# LCmeter0-perfboard-new.net
KiCad netlist of a schematic drawn in EAGLE
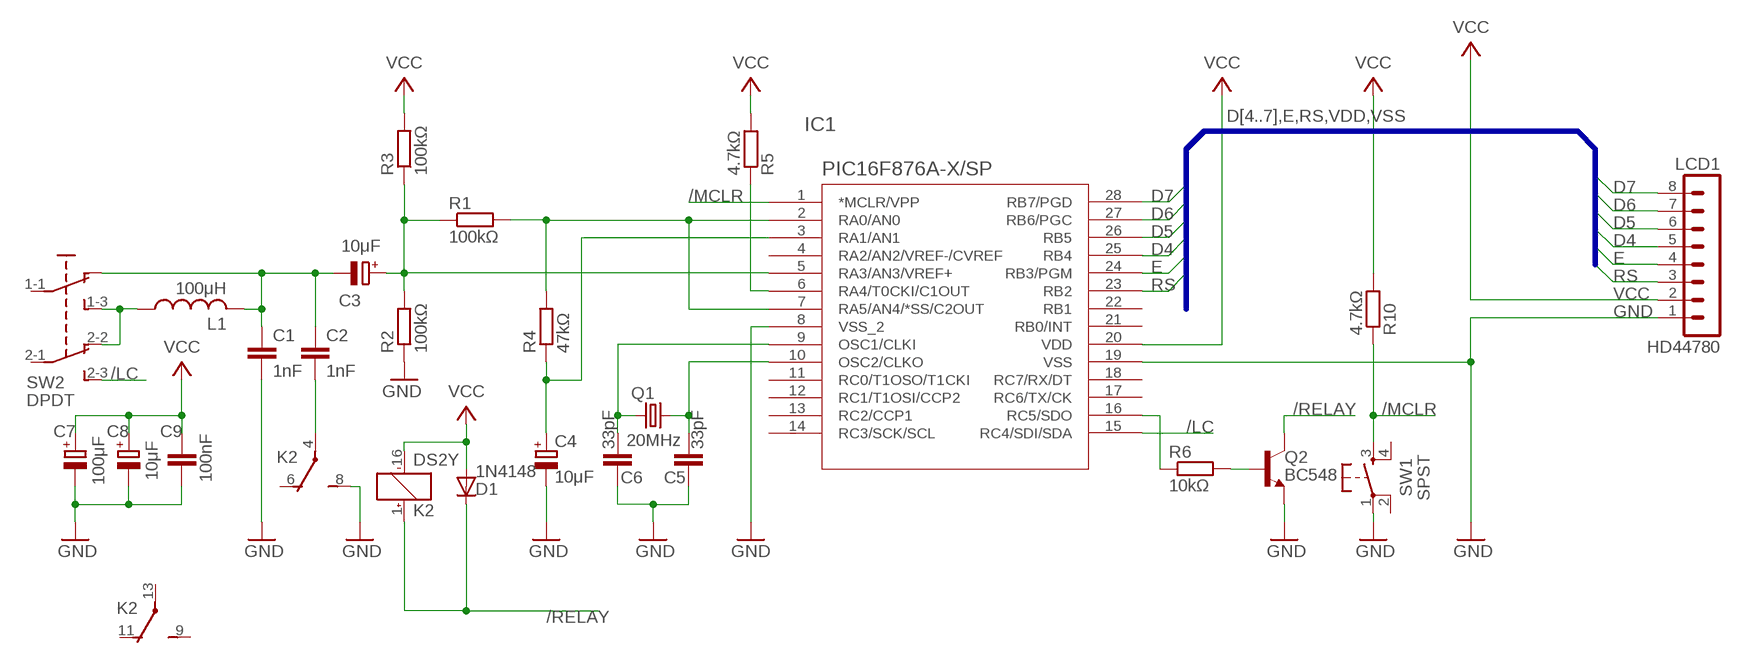
[diagram p0: schematic, sheet 1]

(export (version "E")
  (design (tool "Eeschema 10.0.6"))
  (components
    (comp (ref "C1")
      (value "1nF")
      (footprint "eagle-import:C050-024X044")
      (libsource (lib "eagle-import") (part "C-EU050-024X044"))
    )
    (comp (ref "C2")
      (value "1nF")
      (footprint "eagle-import:C050-024X044")
      (libsource (lib "eagle-import") (part "C-EU050-024X044"))
    )
    (comp (ref "C3")
      (value "10μF")
      (footprint "eagle-import:E5-4")
      (libsource (lib "eagle-import") (part "CPOL-EUE5-4"))
    )
    (comp (ref "C4")
      (value "10μF")
      (footprint "eagle-import:E5-4")
      (libsource (lib "eagle-import") (part "CPOL-EUE5-4"))
    )
    (comp (ref "C5")
      (value "33pF")
      (footprint "eagle-import:C050-024X044")
      (libsource (lib "eagle-import") (part "C-EU050-024X044"))
    )
    (comp (ref "C6")
      (value "33pF")
      (footprint "eagle-import:C050-024X044")
      (libsource (lib "eagle-import") (part "C-EU050-024X044"))
    )
    (comp (ref "C7")
      (value "100μF")
      (footprint "eagle-import:E2,5-6")
      (libsource (lib "eagle-import") (part "CPOL-EUE2.5-6"))
    )
    (comp (ref "C8")
      (value "10μF")
      (footprint "eagle-import:E2,5-5")
      (libsource (lib "eagle-import") (part "CPOL-EUE2.5-5"))
    )
    (comp (ref "C9")
      (value "100nF")
      (footprint "eagle-import:C025-024X044")
      (libsource (lib "eagle-import") (part "C-EU025-024X044"))
    )
    (comp (ref "D1")
      (value "1N4148")
      (footprint "eagle-import:DO35-7")
      (libsource (lib "eagle-import") (part "1N4148DO35-7"))
    )
    (comp (ref "IC1")
      (value "PIC16F876A-X/SP")
      (footprint "eagle-import:DIL28-3")
      (libsource (lib "eagle-import") (part "PIC16F876A-X/SP"))
    )
    (comp (ref "K2")
      (value "DS2Y")
      (footprint "eagle-import:DS2Y")
      (fields (field (name "MPN") "DS2Y-S-DC5V"))
      (libsource (lib "eagle-import") (part "DS2Y-S-DC5V"))
    )
    (comp (ref "L1")
      (value "100μH")
      (footprint "eagle-import:0204_5")
      (libsource (lib "eagle-import") (part "L-US0204/5"))
    )
    (comp (ref "LCD1")
      (value "HD44780")
      (footprint "eagle-import:MA08-1")
      (libsource (lib "eagle-import") (part "MA08-1"))
    )
    (comp (ref "Q1")
      (value "20MHz")
      (footprint "eagle-import:HC49_S")
      (libsource (lib "eagle-import") (part "CRYSTALHC49S"))
    )
    (comp (ref "Q2")
      (value "BC548")
      (footprint "eagle-import:TO92-EBC")
      (libsource (lib "eagle-import") (part "BC548"))
    )
    (comp (ref "R1")
      (value "100kΩ")
      (footprint "eagle-import:0204_7")
      (libsource (lib "eagle-import") (part "R-EU_0204/7"))
    )
    (comp (ref "R2")
      (value "100kΩ")
      (footprint "eagle-import:0204V")
      (libsource (lib "eagle-import") (part "resistor_R-EU_0204/2V"))
    )
    (comp (ref "R3")
      (value "100kΩ")
      (footprint "eagle-import:0204V")
      (libsource (lib "eagle-import") (part "resistor_R-EU_0204/2V"))
    )
    (comp (ref "R4")
      (value "47kΩ")
      (footprint "eagle-import:0204V")
      (libsource (lib "eagle-import") (part "resistor_R-EU_0204/2V"))
    )
    (comp (ref "R5")
      (value "4.7kΩ")
      (footprint "eagle-import:0207_10")
      (libsource (lib "eagle-import") (part "resistor_R-EU_0207/10"))
    )
    (comp (ref "R6")
      (value "10kΩ")
      (footprint "eagle-import:0204V")
      (libsource (lib "eagle-import") (part "resistor_R-EU_0204/2V"))
    )
    (comp (ref "R10")
      (value "4.7kΩ")
      (footprint "eagle-import:0207_10")
      (libsource (lib "eagle-import") (part "resistor_R-EU_0207/10"))
    )
    (comp (ref "SW1")
      (value "SPST")
      (footprint "eagle-import:PB-5")
      (libsource (lib "eagle-import") (part "PB-SPST"))
    )
    (comp (ref "SW2")
      (value "DPDT")
      (footprint "eagle-import:DPDT")
      (libsource (lib "eagle-import") (part "S-DPDT"))
    )
  )
  (nets
    (net (code "3") (name "/D4") (class "Default")
      (node (ref "IC1") (pin "25") (pinfunction "RB4_25") (pintype "passive"))
      (node (ref "LCD1") (pin "5") (pinfunction "5_5") (pintype "passive"))
    )
    (net (code "4") (name "/D5") (class "Default")
      (node (ref "IC1") (pin "26") (pinfunction "RB5_26") (pintype "passive"))
      (node (ref "LCD1") (pin "6") (pinfunction "6_6") (pintype "passive"))
    )
    (net (code "5") (name "/D6") (class "Default")
      (node (ref "IC1") (pin "27") (pinfunction "RB6/PGC_27") (pintype "passive"))
      (node (ref "LCD1") (pin "7") (pinfunction "7_7") (pintype "passive"))
    )
    (net (code "6") (name "/D7") (class "Default")
      (node (ref "IC1") (pin "28") (pinfunction "RB7/PGD_28") (pintype "passive"))
      (node (ref "LCD1") (pin "8") (pinfunction "8_8") (pintype "passive"))
    )
    (net (code "7") (name "/E") (class "Default")
      (node (ref "IC1") (pin "24") (pinfunction "RB3/PGM_24") (pintype "passive"))
      (node (ref "LCD1") (pin "4") (pinfunction "4_4") (pintype "passive"))
    )
    (net (code "8") (name "/RS") (class "Default")
      (node (ref "IC1") (pin "23") (pinfunction "RB2_23") (pintype "passive"))
      (node (ref "LCD1") (pin "3") (pinfunction "3_3") (pintype "passive"))
    )
    (net (code "10") (name "/{slash}LC") (class "Default")
      (node (ref "IC1") (pin "15") (pinfunction "RC4/SDI/SDA_15") (pintype "passive"))
      (node (ref "SW2") (pin "2-3") (pinfunction "2-3_2-3") (pintype "passive"))
    )
    (net (code "11") (name "/{slash}MCLR") (class "Default")
      (node (ref "IC1") (pin "1") (pinfunction "*MCLR/VPP_1") (pintype "passive"))
      (node (ref "R10") (pin "1") (pinfunction "1_1") (pintype "passive"))
      (node (ref "SW1") (pin "3") (pinfunction "S_3") (pintype "passive"))
    )
    (net (code "12") (name "/{slash}RELAY") (class "Default")
      (node (ref "D1") (pin "C") (pinfunction "C_C") (pintype "passive"))
      (node (ref "K2") (pin "1") (pinfunction "+_1") (pintype "passive"))
      (node (ref "Q2") (pin "C") (pinfunction "C_C") (pintype "passive"))
    )
    (net (code "13") (name "GND") (class "Default")
      (node (ref "C1") (pin "2") (pinfunction "2_2") (pintype "passive"))
      (node (ref "C4") (pin "-") (pinfunction "-_-") (pintype "passive"))
      (node (ref "C5") (pin "1") (pinfunction "1_1") (pintype "passive"))
      (node (ref "C6") (pin "1") (pinfunction "1_1") (pintype "passive"))
      (node (ref "C7") (pin "-") (pinfunction "-_-") (pintype "passive"))
      (node (ref "C8") (pin "-") (pinfunction "-_-") (pintype "passive"))
      (node (ref "C9") (pin "2") (pinfunction "2_2") (pintype "passive"))
      (node (ref "IC1") (pin "19") (pinfunction "VSS_19") (pintype "passive"))
      (node (ref "IC1") (pin "8") (pinfunction "VSS_2_8") (pintype "passive"))
      (node (ref "K2") (pin "8") (pinfunction "S_8") (pintype "passive"))
      (node (ref "LCD1") (pin "1") (pinfunction "1_1") (pintype "passive"))
      (node (ref "Q2") (pin "E") (pinfunction "E_E") (pintype "passive"))
      (node (ref "R2") (pin "1") (pinfunction "1_1") (pintype "passive"))
      (node (ref "SW1") (pin "1") (pinfunction "P_1") (pintype "passive"))
    )
    (net (code "14") (name "Net-(C1-Pad1)") (class "Default")
      (node (ref "C1") (pin "1") (pinfunction "1_1") (pintype "passive"))
      (node (ref "C2") (pin "1") (pinfunction "1_1") (pintype "passive"))
      (node (ref "C3") (pin "-") (pinfunction "-_-") (pintype "passive"))
      (node (ref "L1") (pin "2") (pinfunction "2_2") (pintype "passive"))
      (node (ref "SW2") (pin "1-2") (pinfunction "1-2_1-2") (pintype "passive"))
    )
    (net (code "15") (name "Net-(IC1-OSC1{slash}CLKI)") (class "Default")
      (node (ref "C6") (pin "2") (pinfunction "2_2") (pintype "passive"))
      (node (ref "IC1") (pin "9") (pinfunction "OSC1/CLKI_9") (pintype "passive"))
      (node (ref "Q1") (pin "1") (pinfunction "1_1") (pintype "passive"))
    )
    (net (code "16") (name "Net-(IC1-OSC2{slash}CLKO)") (class "Default")
      (node (ref "C5") (pin "2") (pinfunction "2_2") (pintype "passive"))
      (node (ref "IC1") (pin "10") (pinfunction "OSC2/CLKO_10") (pintype "passive"))
      (node (ref "Q1") (pin "2") (pinfunction "2_2") (pintype "passive"))
    )
    (net (code "17") (name "Net-(IC1-RA0{slash}AN0)") (class "Default")
      (node (ref "IC1") (pin "2") (pinfunction "RA0/AN0_2") (pintype "passive"))
      (node (ref "IC1") (pin "7") (pinfunction "RA5/AN4/*SS/C2OUT_7") (pintype "passive"))
      (node (ref "R1") (pin "2") (pinfunction "2_2") (pintype "passive"))
      (node (ref "R4") (pin "2") (pinfunction "2_2") (pintype "passive"))
    )
    (net (code "18") (name "Net-(IC1-RA1{slash}AN1)") (class "Default")
      (node (ref "C4") (pin "+") (pinfunction "+_+") (pintype "passive"))
      (node (ref "IC1") (pin "3") (pinfunction "RA1/AN1_3") (pintype "passive"))
      (node (ref "R4") (pin "1") (pinfunction "1_1") (pintype "passive"))
    )
    (net (code "19") (name "Net-(IC1-RA3{slash}AN3{slash}VREF+)") (class "Default")
      (node (ref "C3") (pin "+") (pinfunction "+_+") (pintype "passive"))
      (node (ref "IC1") (pin "5") (pinfunction "RA3/AN3/VREF+_5") (pintype "passive"))
      (node (ref "R1") (pin "1") (pinfunction "1_1") (pintype "passive"))
      (node (ref "R2") (pin "2") (pinfunction "2_2") (pintype "passive"))
      (node (ref "R3") (pin "1") (pinfunction "1_1") (pintype "passive"))
    )
    (net (code "20") (name "Net-(IC1-RA4{slash}T0CKI{slash}C1OUT)") (class "Default")
      (node (ref "IC1") (pin "6") (pinfunction "RA4/T0CKI/C1OUT_6") (pintype "passive"))
      (node (ref "R5") (pin "1") (pinfunction "1_1") (pintype "passive"))
    )
    (net (code "21") (name "Net-(IC1-RC5{slash}SDO)") (class "Default")
      (node (ref "IC1") (pin "16") (pinfunction "RC5/SDO_16") (pintype "passive"))
      (node (ref "R6") (pin "1") (pinfunction "1_1") (pintype "passive"))
    )
    (net (code "22") (name "Net-(K2B-P)") (class "Default")
      (node (ref "C2") (pin "2") (pinfunction "2_2") (pintype "passive"))
      (node (ref "K2") (pin "4") (pinfunction "P_4") (pintype "passive"))
    )
    (net (code "23") (name "Net-(L1-Pad1)") (class "Default")
      (node (ref "L1") (pin "1") (pinfunction "1_1") (pintype "passive"))
      (node (ref "SW2") (pin "1-3") (pinfunction "1-3_1-3") (pintype "passive"))
      (node (ref "SW2") (pin "2-2") (pinfunction "2-2_2-2") (pintype "passive"))
    )
    (net (code "24") (name "Net-(Q2-PadB)") (class "Default")
      (node (ref "Q2") (pin "B") (pinfunction "B_B") (pintype "passive"))
      (node (ref "R6") (pin "2") (pinfunction "2_2") (pintype "passive"))
    )
    (net (code "25") (name "VCC") (class "Default")
      (node (ref "C7") (pin "+") (pinfunction "+_+") (pintype "passive"))
      (node (ref "C8") (pin "+") (pinfunction "+_+") (pintype "passive"))
      (node (ref "C9") (pin "1") (pinfunction "1_1") (pintype "passive"))
      (node (ref "D1") (pin "A") (pinfunction "A_A") (pintype "passive"))
      (node (ref "IC1") (pin "20") (pinfunction "VDD_20") (pintype "passive"))
      (node (ref "K2") (pin "16") (pinfunction "-_16") (pintype "passive"))
      (node (ref "LCD1") (pin "2") (pinfunction "2_2") (pintype "passive"))
      (node (ref "R10") (pin "2") (pinfunction "2_2") (pintype "passive"))
      (node (ref "R3") (pin "2") (pinfunction "2_2") (pintype "passive"))
      (node (ref "R5") (pin "2") (pinfunction "2_2") (pintype "passive"))
    )
    (net (code "26") (name "unconnected-(IC1-RA2{slash}AN2{slash}VREF-{slash}CVREF-Pad4)") (class "Default")
      (node (ref "IC1") (pin "4") (pinfunction "RA2/AN2/VREF-/CVREF_4") (pintype "passive"))
    )
    (net (code "27") (name "unconnected-(IC1-RB0{slash}INT-Pad21)") (class "Default")
      (node (ref "IC1") (pin "21") (pinfunction "RB0/INT_21") (pintype "passive"))
    )
    (net (code "28") (name "unconnected-(IC1-RB1-Pad22)") (class "Default")
      (node (ref "IC1") (pin "22") (pinfunction "RB1_22") (pintype "passive"))
    )
    (net (code "29") (name "unconnected-(IC1-RC0{slash}T1OSO{slash}T1CKI-Pad11)") (class "Default")
      (node (ref "IC1") (pin "11") (pinfunction "RC0/T1OSO/T1CKI_11") (pintype "passive"))
    )
    (net (code "30") (name "unconnected-(IC1-RC1{slash}T1OSI{slash}CCP2-Pad12)") (class "Default")
      (node (ref "IC1") (pin "12") (pinfunction "RC1/T1OSI/CCP2_12") (pintype "passive"))
    )
    (net (code "31") (name "unconnected-(IC1-RC2{slash}CCP1-Pad13)") (class "Default")
      (node (ref "IC1") (pin "13") (pinfunction "RC2/CCP1_13") (pintype "passive"))
    )
    (net (code "32") (name "unconnected-(IC1-RC3{slash}SCK{slash}SCL-Pad14)") (class "Default")
      (node (ref "IC1") (pin "14") (pinfunction "RC3/SCK/SCL_14") (pintype "passive"))
    )
    (net (code "33") (name "unconnected-(IC1-RC6{slash}TX{slash}CK-Pad17)") (class "Default")
      (node (ref "IC1") (pin "17") (pinfunction "RC6/TX/CK_17") (pintype "passive"))
    )
    (net (code "34") (name "unconnected-(IC1-RC7{slash}RX{slash}DT-Pad18)") (class "Default")
      (node (ref "IC1") (pin "18") (pinfunction "RC7/RX/DT_18") (pintype "passive"))
    )
    (net (code "35") (name "unconnected-(K2B-O-Pad6)") (class "Default")
      (node (ref "K2") (pin "6") (pinfunction "O_6") (pintype "passive"))
    )
    (net (code "36") (name "unconnected-(K2C-O-Pad11)") (class "Default")
      (node (ref "K2") (pin "11") (pinfunction "O_11") (pintype "passive"))
    )
    (net (code "37") (name "unconnected-(K2C-P-Pad13)") (class "Default")
      (node (ref "K2") (pin "13") (pinfunction "P_13") (pintype "passive"))
    )
    (net (code "38") (name "unconnected-(K2C-S-Pad9)") (class "Default")
      (node (ref "K2") (pin "9") (pinfunction "S_9") (pintype "passive"))
    )
    (net (code "39") (name "unconnected-(SW1-P1-Pad2)") (class "Default")
      (node (ref "SW1") (pin "2") (pinfunction "P1_2") (pintype "passive"))
    )
    (net (code "40") (name "unconnected-(SW1-S1-Pad4)") (class "Default")
      (node (ref "SW1") (pin "4") (pinfunction "S1_4") (pintype "passive"))
    )
    (net (code "41") (name "unconnected-(SW2-Pad1-1)") (class "Default")
      (node (ref "SW2") (pin "1-1") (pinfunction "1-1_1-1") (pintype "passive"))
    )
    (net (code "42") (name "unconnected-(SW2-Pad2-1)") (class "Default")
      (node (ref "SW2") (pin "2-1") (pinfunction "2-1_2-1") (pintype "passive"))
    )
  )
)
